# SparkFun_TPL5110_Nano_Power_Switch.net
KiCad netlist of a schematic drawn in EAGLE
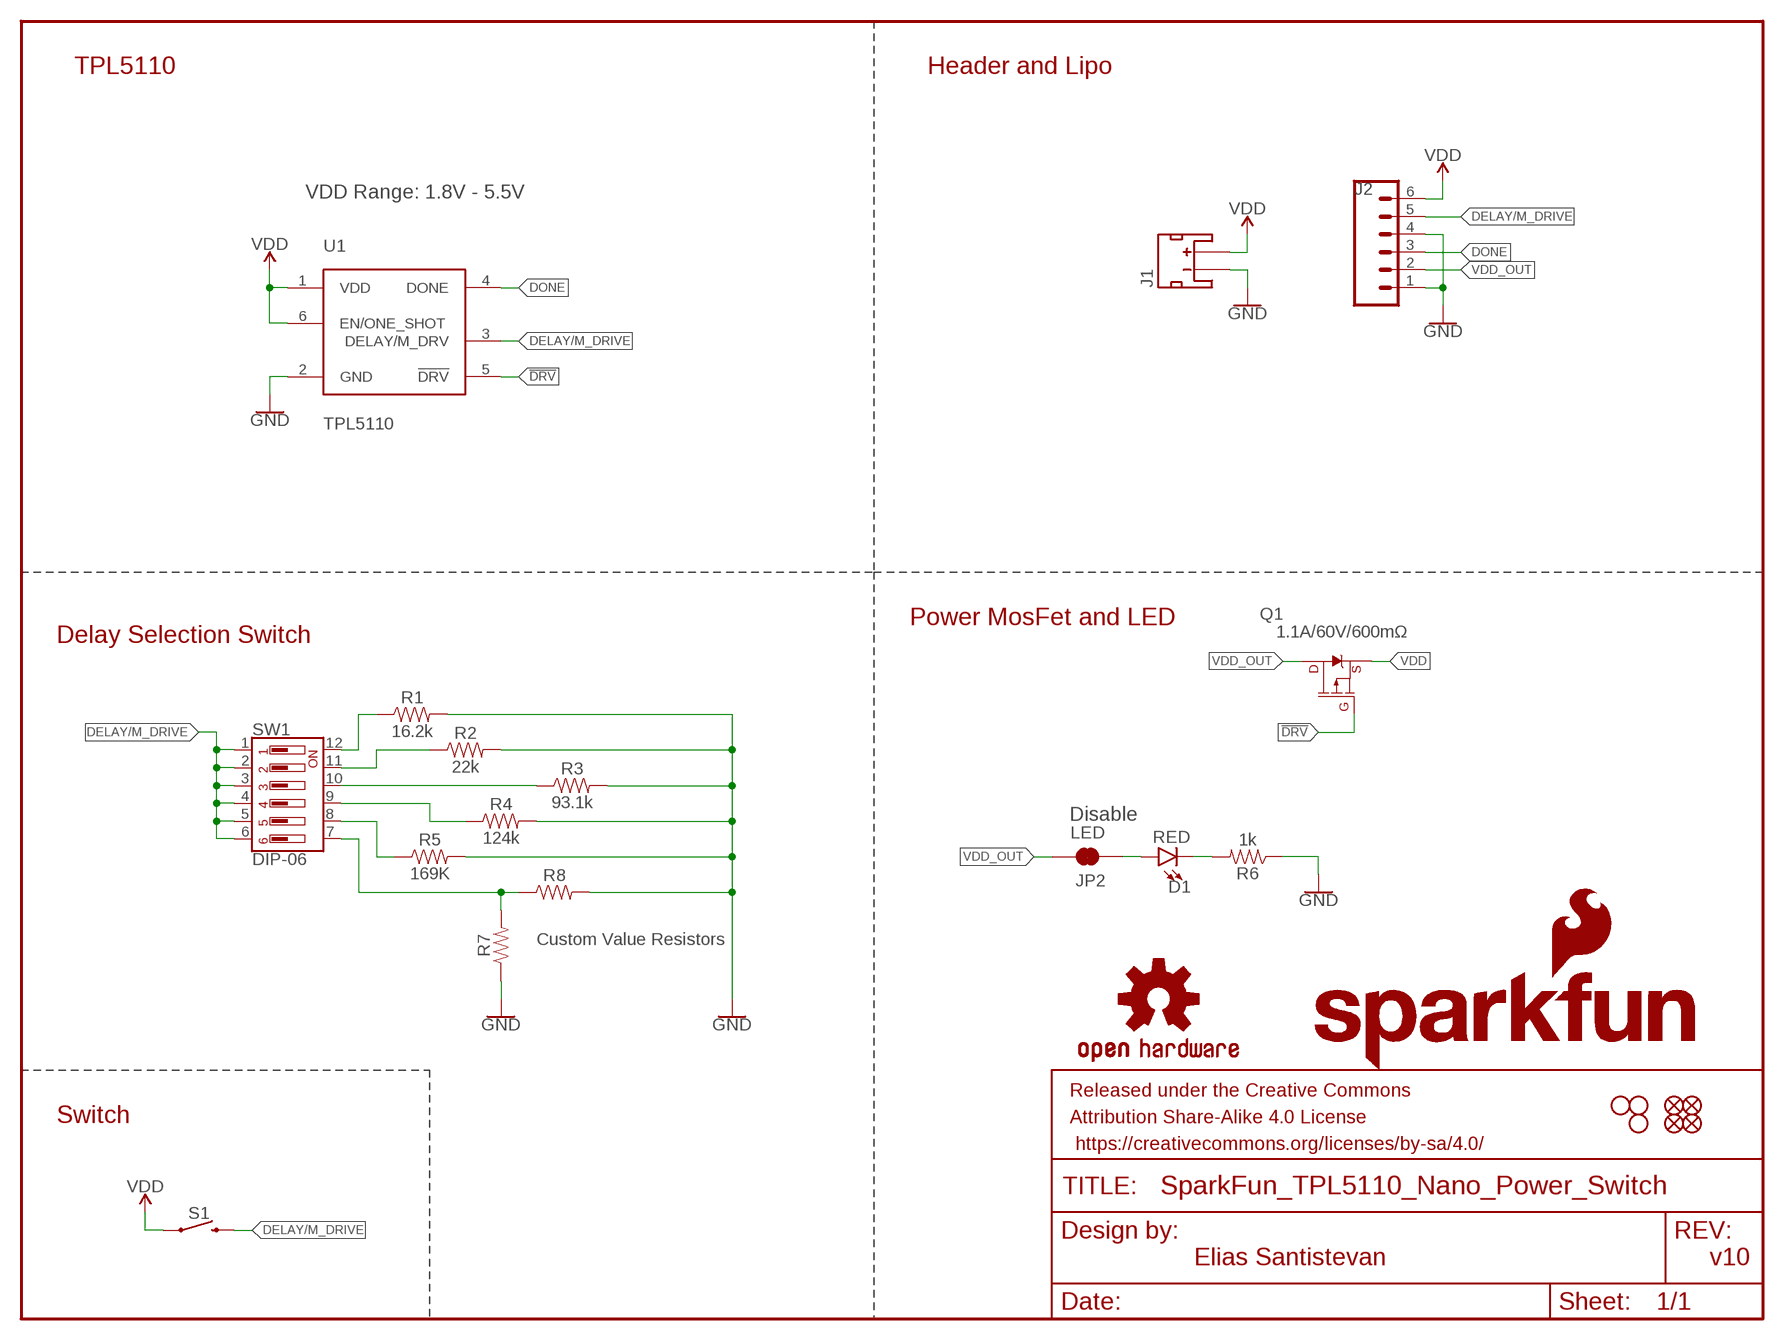
[diagram p0: schematic, sheet 1]

(export (version "E")
  (design (tool "Eeschema 10.0.6"))
  (components
    (comp (ref "D1")
      (value "RED")
      (footprint "eagle-import:LED-0603")
      (libsource (lib "eagle-import") (part "LED-RED0603"))
    )
    (comp (ref "FD1")
      (value "FIDUCIALUFIDUCIAL")
      (footprint "eagle-import:FIDUCIAL-MICRO")
      (libsource (lib "eagle-import") (part "FIDUCIALUFIDUCIAL"))
    )
    (comp (ref "FD2")
      (value "FIDUCIALUFIDUCIAL")
      (footprint "eagle-import:FIDUCIAL-MICRO")
      (libsource (lib "eagle-import") (part "FIDUCIALUFIDUCIAL"))
    )
    (comp (ref "FD3")
      (value "FIDUCIALUFIDUCIAL")
      (footprint "eagle-import:FIDUCIAL-MICRO")
      (libsource (lib "eagle-import") (part "FIDUCIALUFIDUCIAL"))
    )
    (comp (ref "FD4")
      (value "FIDUCIALUFIDUCIAL")
      (footprint "eagle-import:FIDUCIAL-MICRO")
      (libsource (lib "eagle-import") (part "FIDUCIALUFIDUCIAL"))
    )
    (comp (ref "FRAME1")
      (value "FRAME-LETTER")
      (footprint "eagle-import:CREATIVE_COMMONS")
      (libsource (lib "eagle-import") (part "FRAME-LETTER"))
    )
    (comp (ref "H1")
      (value "STAND-OFFTIGHT")
      (footprint "eagle-import:STAND-OFF-TIGHT")
      (libsource (lib "eagle-import") (part "STAND-OFFTIGHT"))
    )
    (comp (ref "H2")
      (value "STAND-OFFTIGHT")
      (footprint "eagle-import:STAND-OFF-TIGHT")
      (libsource (lib "eagle-import") (part "STAND-OFFTIGHT"))
    )
    (comp (ref "H4")
      (value "STAND-OFFTIGHT")
      (footprint "eagle-import:STAND-OFF-TIGHT")
      (libsource (lib "eagle-import") (part "STAND-OFFTIGHT"))
    )
    (comp (ref "J1")
      (value "JST_2MM_MALE")
      (footprint "eagle-import:JST-2-SMD")
      (libsource (lib "eagle-import") (part "JST_2MM_MALE"))
    )
    (comp (ref "J2")
      (value "CONN_06NO_SILK_NO_POP")
      (footprint "eagle-import:1X06_NO_SILK")
      (libsource (lib "eagle-import") (part "CONN_06NO_SILK_NO_POP"))
    )
    (comp (ref "JP2")
      (value "LED")
      (footprint "eagle-import:SMT-JUMPER_2_NC_TRACE_SILK")
      (libsource (lib "eagle-import") (part "JUMPER-SMT_2_NC_TRACE_SILK"))
    )
    (comp (ref "LOGO1")
      (value "SFE_LOGO_NAME.1_INCH")
      (footprint "eagle-import:SFE_LOGO_NAME_.1")
      (libsource (lib "eagle-import") (part "SFE_LOGO_NAME.1_INCH"))
    )
    (comp (ref "LOGO2")
      (value "OSHW-LOGOS")
      (footprint "eagle-import:OSHW-LOGO-S")
      (libsource (lib "eagle-import") (part "OSHW-LOGOS"))
    )
    (comp (ref "LOGO3")
      (value "SFE_LOGO_FLAME.1_INCH")
      (footprint "eagle-import:SFE_LOGO_FLAME_.1")
      (libsource (lib "eagle-import") (part "SFE_LOGO_FLAME.1_INCH"))
    )
    (comp (ref "Q1")
      (value "1.1A/60V/600mΩ")
      (footprint "eagle-import:SOT23-3")
      (libsource (lib "eagle-import") (part "MOSFET_PCH-SI2309DS"))
    )
    (comp (ref "R1")
      (value "16.2k")
      (footprint "eagle-import:0603")
      (libsource (lib "eagle-import") (part "16.2KOHM-0603-1/10W-1%"))
    )
    (comp (ref "R2")
      (value "22k")
      (footprint "eagle-import:0603")
      (libsource (lib "eagle-import") (part "22KOHM-0603-1/10W-1%"))
    )
    (comp (ref "R3")
      (value "93.1k")
      (footprint "eagle-import:0603")
      (libsource (lib "eagle-import") (part "93.1KOHM"))
    )
    (comp (ref "R4")
      (value "124k")
      (footprint "eagle-import:0603")
      (libsource (lib "eagle-import") (part "124KOHM"))
    )
    (comp (ref "R5")
      (value "169K")
      (footprint "eagle-import:0603")
      (libsource (lib "eagle-import") (part "169KOHM"))
    )
    (comp (ref "R6")
      (value "1k")
      (footprint "eagle-import:0603")
      (libsource (lib "eagle-import") (part "1KOHM-0603-1/10W-1%"))
    )
    (comp (ref "R7")
      (value "RESISTOR0603")
      (footprint "eagle-import:0603")
      (libsource (lib "eagle-import") (part "RESISTOR0603"))
    )
    (comp (ref "R8")
      (value "RESISTORAXIAL-0.3")
      (footprint "eagle-import:AXIAL-0.3")
      (libsource (lib "eagle-import") (part "RESISTORAXIAL-0.3"))
    )
    (comp (ref "S1")
      (value "MOMENTARY-SWITCH-SPST-SMD-5.2MM-TALL")
      (footprint "eagle-import:TACTILE_SWITCH_SMD_5.2MM")
      (libsource (lib "eagle-import") (part "MOMENTARY-SWITCH-SPST-SMD-5.2MM-TALL"))
    )
    (comp (ref "SW1")
      (value "DIP-06")
      (footprint "eagle-import:DIPSWITCH-06-SMD")
      (libsource (lib "eagle-import") (part "DIP-06"))
    )
    (comp (ref "U1")
      (value "TPL5110")
      (footprint "eagle-import:SOT23-6")
      (libsource (lib "eagle-import") (part "TPL5110"))
    )
  )
  (nets
    (net (code "1") (name "/~{DRV}") (class "Default")
      (node (ref "Q1") (pin "1") (pinfunction "G_1") (pintype "bidirectional"))
      (node (ref "U1") (pin "5") (pinfunction "~{DRV}_5") (pintype "output"))
    )
    (net (code "2") (name "DELAY{slash}M_DRIVE") (class "Default")
      (node (ref "J2") (pin "5") (pinfunction "5_5") (pintype "passive"))
      (node (ref "S1") (pin "3") (pinfunction "2_3") (pintype "passive"))
      (node (ref "SW1") (pin "1") (pinfunction "1_1") (pintype "bidirectional"))
      (node (ref "SW1") (pin "2") (pinfunction "2_2") (pintype "bidirectional"))
      (node (ref "SW1") (pin "3") (pinfunction "3_3") (pintype "bidirectional"))
      (node (ref "SW1") (pin "4") (pinfunction "4_4") (pintype "bidirectional"))
      (node (ref "SW1") (pin "5") (pinfunction "5_5") (pintype "bidirectional"))
      (node (ref "SW1") (pin "6") (pinfunction "6_6") (pintype "bidirectional"))
      (node (ref "U1") (pin "3") (pinfunction "DELAY/M_DRV_3") (pintype "input"))
    )
    (net (code "3") (name "DONE") (class "Default")
      (node (ref "J2") (pin "3") (pinfunction "3_3") (pintype "passive"))
      (node (ref "U1") (pin "4") (pinfunction "DONE_4") (pintype "input"))
    )
    (net (code "4") (name "GND") (class "Default")
      (node (ref "J1") (pin "1") (pinfunction "-_1") (pintype "bidirectional"))
      (node (ref "J2") (pin "1") (pinfunction "1_1") (pintype "passive"))
      (node (ref "J2") (pin "4") (pinfunction "4_4") (pintype "passive"))
      (node (ref "R1") (pin "2") (pinfunction "2_2") (pintype "passive"))
      (node (ref "R2") (pin "2") (pinfunction "2_2") (pintype "passive"))
      (node (ref "R3") (pin "2") (pinfunction "2_2") (pintype "passive"))
      (node (ref "R4") (pin "2") (pinfunction "2_2") (pintype "passive"))
      (node (ref "R5") (pin "2") (pinfunction "2_2") (pintype "passive"))
      (node (ref "R6") (pin "1") (pinfunction "1_1") (pintype "passive"))
      (node (ref "R7") (pin "1") (pinfunction "1_1") (pintype "passive"))
      (node (ref "R8") (pin "P$2") (pinfunction "2_P$2") (pintype "passive"))
      (node (ref "U1") (pin "2") (pinfunction "GND_2") (pintype "power_in"))
    )
    (net (code "5") (name "Net-(D1-PadA)") (class "Default")
      (node (ref "D1") (pin "A") (pinfunction "A_A") (pintype "passive"))
      (node (ref "JP2") (pin "1") (pinfunction "1_1") (pintype "passive"))
    )
    (net (code "6") (name "Net-(D1-PadC)") (class "Default")
      (node (ref "D1") (pin "C") (pinfunction "C_C") (pintype "passive"))
      (node (ref "R6") (pin "2") (pinfunction "2_2") (pintype "passive"))
    )
    (net (code "7") (name "Net-(R1-Pad1)") (class "Default")
      (node (ref "R1") (pin "1") (pinfunction "1_1") (pintype "passive"))
      (node (ref "SW1") (pin "12") (pinfunction "12_12") (pintype "bidirectional"))
    )
    (net (code "8") (name "Net-(R2-Pad1)") (class "Default")
      (node (ref "R2") (pin "1") (pinfunction "1_1") (pintype "passive"))
      (node (ref "SW1") (pin "11") (pinfunction "11_11") (pintype "bidirectional"))
    )
    (net (code "9") (name "Net-(R3-Pad1)") (class "Default")
      (node (ref "R3") (pin "1") (pinfunction "1_1") (pintype "passive"))
      (node (ref "SW1") (pin "10") (pinfunction "10_10") (pintype "bidirectional"))
    )
    (net (code "10") (name "Net-(R4-Pad1)") (class "Default")
      (node (ref "R4") (pin "1") (pinfunction "1_1") (pintype "passive"))
      (node (ref "SW1") (pin "9") (pinfunction "9_9") (pintype "bidirectional"))
    )
    (net (code "11") (name "Net-(R5-Pad1)") (class "Default")
      (node (ref "R5") (pin "1") (pinfunction "1_1") (pintype "passive"))
      (node (ref "SW1") (pin "8") (pinfunction "8_8") (pintype "bidirectional"))
    )
    (net (code "12") (name "Net-(R8-1)") (class "Default")
      (node (ref "R7") (pin "2") (pinfunction "2_2") (pintype "passive"))
      (node (ref "R8") (pin "P$1") (pinfunction "1_P$1") (pintype "passive"))
      (node (ref "SW1") (pin "7") (pinfunction "7_7") (pintype "bidirectional"))
    )
    (net (code "13") (name "VDD") (class "Default")
      (node (ref "J1") (pin "2") (pinfunction "+_2") (pintype "bidirectional"))
      (node (ref "J2") (pin "6") (pinfunction "6_6") (pintype "passive"))
      (node (ref "Q1") (pin "2") (pinfunction "S_2") (pintype "bidirectional"))
      (node (ref "S1") (pin "1") (pinfunction "1_1") (pintype "passive"))
      (node (ref "U1") (pin "1") (pinfunction "VDD_1") (pintype "power_in"))
      (node (ref "U1") (pin "6") (pinfunction "EN/ONE_SHOT_6") (pintype "input"))
    )
    (net (code "14") (name "VDD_OUT") (class "Default")
      (node (ref "J2") (pin "2") (pinfunction "2_2") (pintype "passive"))
      (node (ref "JP2") (pin "2") (pinfunction "2_2") (pintype "passive"))
      (node (ref "Q1") (pin "3") (pinfunction "D_3") (pintype "bidirectional"))
    )
    (net (code "15") (name "unconnected-(J1-PAD1-PadNC1)") (class "Default")
      (node (ref "J1") (pin "NC1") (pinfunction "PAD1_NC1") (pintype "bidirectional"))
    )
    (net (code "16") (name "unconnected-(J1-PAD2-PadNC2)") (class "Default")
      (node (ref "J1") (pin "NC2") (pinfunction "PAD2_NC2") (pintype "bidirectional"))
    )
  )
)
